# rtc_accel.net
KiCad netlist of a schematic drawn in Altium Designer
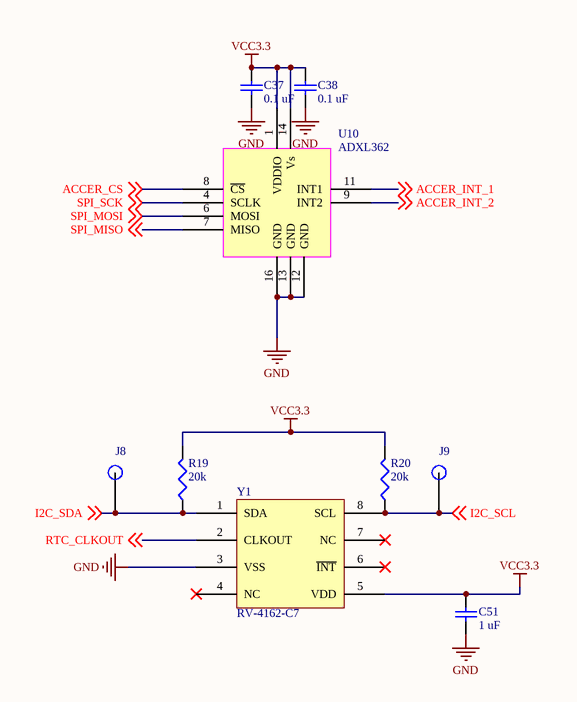
[diagram p0: rtc_accel.SchDoc]

(export (version "E")
  (design (tool "Eeschema 10.0.6"))
  (components
    (comp (ref "C37")
      (value "0.1 uF")
      (footprint "0402")
      (description "Ceramic capacitor, 0.1u, 0402 package")
      (fields (field (name "TOLERANCE") "10%") (field (name "Comment") "Ceramic capacitor"))
      (libsource (lib "rlc") (part "C_0.1u_0402_ceramic"))
    )
    (comp (ref "C38")
      (value "0.1 uF")
      (footprint "0402")
      (description "Ceramic capacitor, 0.1u, 0402 package")
      (fields (field (name "TOLERANCE") "10%") (field (name "Comment") "Ceramic capacitor"))
      (libsource (lib "rlc") (part "C_0.1u_0402_ceramic"))
    )
    (comp (ref "C51")
      (value "1 uF")
      (footprint "0402")
      (description "Ceramic capacitor, 1 uF, 0402 package")
      (fields (field (name "TOLERANCE") "10%") (field (name "Comment") "Ceramic capacitor"))
      (libsource (lib "rlc") (part "C_1u_0402_ceramic"))
    )
    (comp (ref "J8")
      (value "RCU 0603 SMD Testpoint")
      (footprint "RCU_0603")
      (description "0603 SMD Testpoint")
      (libsource (lib "connectors") (part "Testpoint-0603"))
    )
    (comp (ref "J9")
      (value "RCU 0603 SMD Testpoint")
      (footprint "RCU_0603")
      (description "0603 SMD Testpoint")
      (libsource (lib "connectors") (part "Testpoint-0603"))
    )
    (comp (ref "R19")
      (value "20k")
      (footprint "0402")
      (description "20k ohm, 0402, 1%, .1W")
      (fields (field (name "Comment") "20k Resistor"))
      (libsource (lib "rlc") (part "R_20K_0402"))
    )
    (comp (ref "R20")
      (value "20k")
      (footprint "0402")
      (description "20k ohm, 0402, 1%, .1W")
      (fields (field (name "Comment") "20k Resistor"))
      (libsource (lib "rlc") (part "R_20K_0402"))
    )
    (comp (ref "U10")
      (value "ADXL362")
      (footprint "LGA_CC-16-4")
      (description "Micropower, 3-Axis, ±2 g/±4 g/±8 g  Digital Output MEMS Accelerometer")
      (libsource (lib "opo") (part "ADXL362"))
    )
    (comp (ref "Y1")
      (value "RV-4162-C7")
      (footprint "RV4162")
      (description "Real Time Clock Module with I2C Bus")
      (libsource (lib "opo") (part "RV-4162-C7"))
    )
  )
  (nets
    (net (code "1") (name "ACCER_CS") (class "Default")
      (node (ref "U10") (pin "8") (pinfunction "~{CS}_8") (pintype "passive"))
    )
    (net (code "2") (name "ACCER_INT_1") (class "Default")
      (node (ref "U10") (pin "11") (pinfunction "INT1_11") (pintype "passive"))
    )
    (net (code "3") (name "ACCER_INT_2") (class "Default")
      (node (ref "U10") (pin "9") (pinfunction "INT2_9") (pintype "passive"))
    )
    (net (code "4") (name "GND") (class "Default")
      (node (ref "C37") (pin "2") (pintype "passive"))
      (node (ref "C38") (pin "2") (pintype "passive"))
      (node (ref "C51") (pin "2") (pintype "passive"))
      (node (ref "U10") (pin "12") (pinfunction "GND_12") (pintype "passive"))
      (node (ref "U10") (pin "13") (pinfunction "GND_13") (pintype "passive"))
      (node (ref "U10") (pin "16") (pinfunction "GND_16") (pintype "passive"))
      (node (ref "Y1") (pin "3") (pinfunction "VSS_3") (pintype "passive"))
    )
    (net (code "5") (name "I2C_SCL") (class "Default")
      (node (ref "J9") (pin "1") (pinfunction "J_1") (pintype "passive"))
      (node (ref "R20") (pin "2") (pintype "passive"))
      (node (ref "Y1") (pin "8") (pinfunction "SCL_8") (pintype "passive"))
    )
    (net (code "6") (name "I2C_SDA") (class "Default")
      (node (ref "J8") (pin "1") (pinfunction "J_1") (pintype "passive"))
      (node (ref "R19") (pin "2") (pintype "passive"))
      (node (ref "Y1") (pin "1") (pinfunction "SDA_1") (pintype "passive"))
    )
    (net (code "7") (name "RTC_CLKOUT") (class "Default")
      (node (ref "Y1") (pin "2") (pinfunction "CLKOUT_2") (pintype "passive"))
    )
    (net (code "8") (name "SPI_MISO") (class "Default")
      (node (ref "U10") (pin "7") (pinfunction "MISO_7") (pintype "passive"))
    )
    (net (code "9") (name "SPI_MOSI") (class "Default")
      (node (ref "U10") (pin "6") (pinfunction "MOSI_6") (pintype "passive"))
    )
    (net (code "10") (name "SPI_SCK") (class "Default")
      (node (ref "U10") (pin "4") (pinfunction "SCLK_4") (pintype "passive"))
    )
    (net (code "11") (name "VCC3.3") (class "Default")
      (node (ref "C37") (pin "1") (pintype "passive"))
      (node (ref "C38") (pin "1") (pintype "passive"))
      (node (ref "C51") (pin "1") (pintype "passive"))
      (node (ref "R19") (pin "1") (pintype "passive"))
      (node (ref "R20") (pin "1") (pintype "passive"))
      (node (ref "U10") (pin "1") (pinfunction "VDDIO_1") (pintype "passive"))
      (node (ref "U10") (pin "14") (pinfunction "Vs_14") (pintype "passive"))
      (node (ref "Y1") (pin "5") (pinfunction "VDD_5") (pintype "passive"))
    )
    (net (code "12") (name "unconnected-(Y1-NC-Pad4)") (class "Default")
      (node (ref "Y1") (pin "4") (pinfunction "NC_4") (pintype "passive+no_connect"))
    )
    (net (code "13") (name "unconnected-(Y1-NC-Pad7)") (class "Default")
      (node (ref "Y1") (pin "7") (pinfunction "NC_7") (pintype "passive+no_connect"))
    )
    (net (code "14") (name "unconnected-(Y1-~{INT}-Pad6)") (class "Default")
      (node (ref "Y1") (pin "6") (pinfunction "~{INT}_6") (pintype "passive+no_connect"))
    )
  )
)
